# Sensor_Sheet.net
KiCad netlist of a schematic drawn in Altium Designer
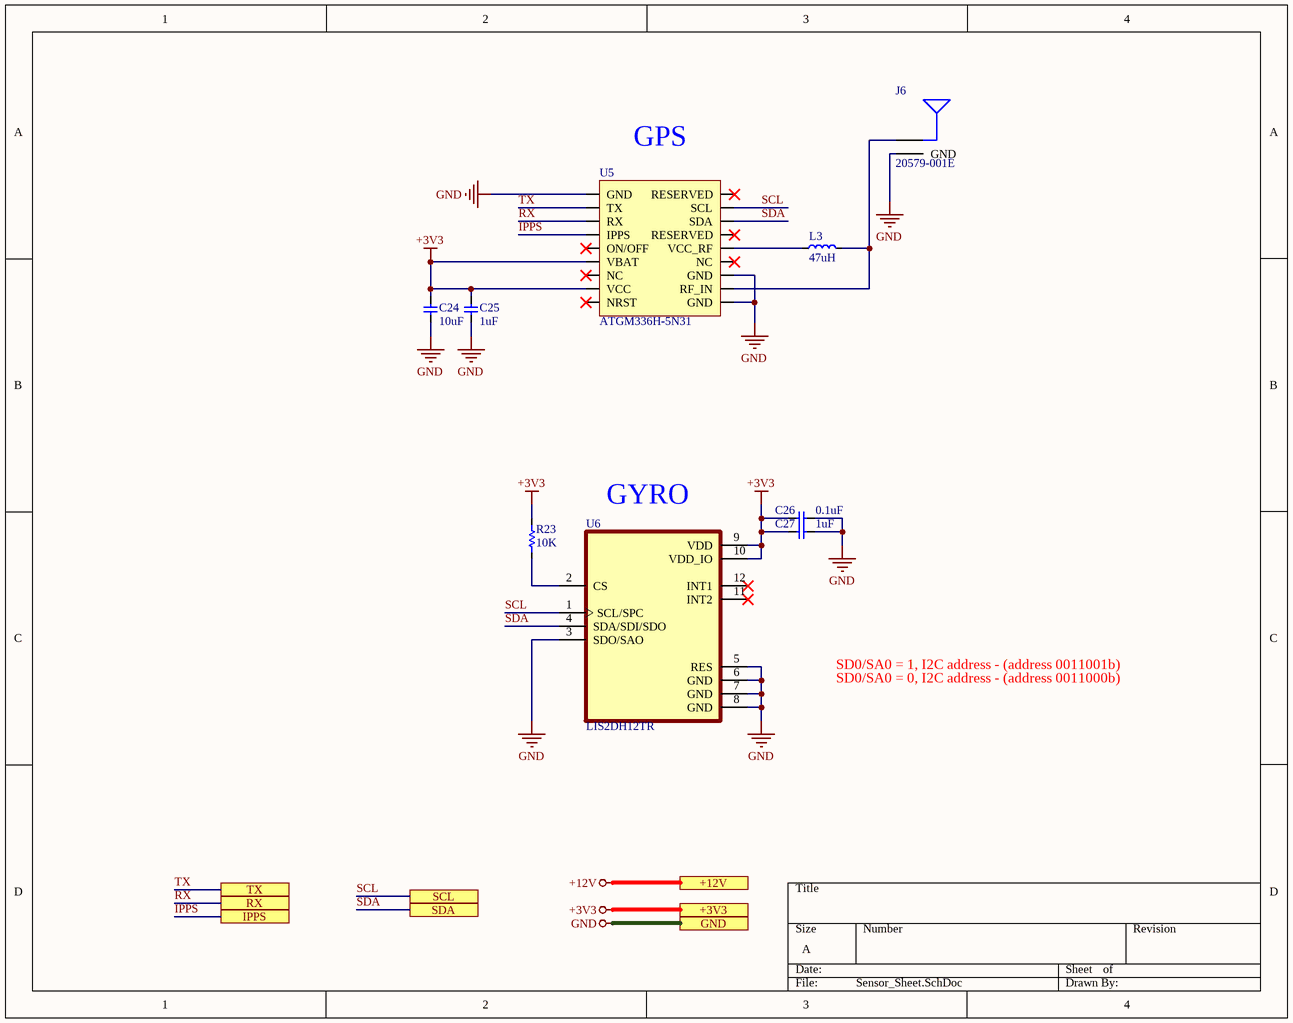
[diagram p0: Sensor_Sheet.SchDoc]

(export (version "E")
  (design (tool "Eeschema 10.0.6"))
  (components
    (comp (ref "C24")
      (value "10uF")
      (footprint "Cap-0603")
      (description "10uF 35V X5R 20% Pad SMD 0603")
      (fields
        (field (name "MANUFACTURER") "Murata")
        (field (name "MANUFACTURER PART NUMBER") "GRM188R6YA106MA73D")
      )
      (libsource (lib "DigitalAzanClock") (part "GRM188R6YA106MA73D"))
    )
    (comp (ref "C25")
      (value "1uF")
      (footprint "Cap-0603")
      (description "CAP CER 1UF 25V X5R 0603")
      (fields
        (field (name "MANUFACTURER") "Yageo")
        (field (name "MANUFACTURER PART NUMBER") "CC0603KRX5R8BB105")
      )
      (libsource (lib "DigitalAzanClock") (part "CC0603KRX5R8BB105"))
    )
    (comp (ref "C26")
      (value "0.1uF")
      (footprint "Cap-0603")
      (description "CAP CER 0.1UF 100V X7R 0603")
      (fields
        (field (name "MANUFACTURER") "Yageo")
        (field (name "MANUFACTURER PART NUMBER") "CC0603KRX7R0BB104")
      )
      (libsource (lib "DigitalAzanClock") (part "CC0603KRX7R0BB104"))
    )
    (comp (ref "C27")
      (value "1uF")
      (footprint "Cap-0603")
      (description "CAP CER 1UF 25V X5R 0603")
      (fields
        (field (name "MANUFACTURER") "Yageo")
        (field (name "MANUFACTURER PART NUMBER") "CC0603KRX5R8BB105")
      )
      (libsource (lib "DigitalAzanClock") (part "CC0603KRX5R8BB105"))
    )
    (comp (ref "J6")
      (value "20579-001E")
      (footprint "IPEX-1")
      (description "The M.2 industry standard,support up to 12 GHz")
      (fields (field (name "MANUFACTURER") "I-PEX") (field (name "LCSC PART NUMBER") "C2987682"))
      (libsource (lib "DigitalAzanClock") (part "IPEX-0001"))
    )
    (comp (ref "L3")
      (value "47uH")
      (footprint "CYA0650-47UH")
      (description "2A 47uH ±20% 250mΩ SMD,6.6x7.2mm Inductors (SMD) ROHS")
      (fields
        (field (name "MANUFACTURER") "SHOU HAN")
        (field (name "MANUFACTURER PART NUMBER") "CYA0650-47UH")
      )
      (libsource (lib "DigitalAzanClock") (part "CYA0650-47UH"))
    )
    (comp (ref "R23")
      (value "10K")
      (footprint "Res-0603")
      (description "RES SMD 10K OHM 0.1% 1/10W 0603")
      (fields
        (field (name "MANUFACTURER") "Yageo")
        (field (name "MANUFACTURER PART NUMBER") "RT0603BRD0710KL")
      )
      (libsource (lib "DigitalAzanClock") (part "RT0603BRD0710KL"))
    )
    (comp (ref "U5")
      (value "ATGM336H-5N31")
      (footprint "ATGM336H")
      (description "SMD,9.7x10.1mm Satellite Positioning Modules ROHS")
      (fields (field (name "MANUFACTURER") "ZHONGKEWEI") (field (name "LCSC PART NUMBER") "C90770"))
      (libsource (lib "DigitalAzanClock") (part "ATGM336H-5N31"))
    )
    (comp (ref "U6")
      (value "LIS2DH12TR")
      (footprint "PQFN50P200X200100-12N")
      (description "Accelerometer X, Y, Z Axis Â±2g, 4g, 8g, 16g 0.5Hz ~ 672Hz 12-LGA (2x2)")
      (fields (field (name "MANUFACTURER") "STMicroelectronics") (field (name "LCSC PART NUMBER") "C110926"))
      (libsource (lib "DigitalAzanClock") (part "LIS2DH12TR"))
    )
  )
  (nets
    (net (code "1") (name "+3V3") (class "Default")
      (node (ref "C24") (pin "2") (pinfunction "2_2") (pintype "passive"))
      (node (ref "C25") (pin "2") (pinfunction "2_2") (pintype "passive"))
      (node (ref "C26") (pin "1") (pinfunction "1_1") (pintype "passive"))
      (node (ref "C27") (pin "1") (pinfunction "1_1") (pintype "passive"))
      (node (ref "R23") (pin "2") (pinfunction "2_2") (pintype "passive"))
      (node (ref "U5") (pin "6") (pinfunction "VBAT_6") (pintype "passive"))
      (node (ref "U5") (pin "8") (pinfunction "VCC_8") (pintype "passive"))
      (node (ref "U6") (pin "10") (pinfunction "VDD_IO_10") (pintype "power_in"))
      (node (ref "U6") (pin "9") (pinfunction "VDD_9") (pintype "power_in"))
    )
    (net (code "3") (name "/IPPS") (class "Default")
      (node (ref "U5") (pin "4") (pinfunction "IPPS_4") (pintype "passive"))
    )
    (net (code "4") (name "/RX") (class "Default")
      (node (ref "U5") (pin "3") (pinfunction "RX_3") (pintype "passive"))
    )
    (net (code "5") (name "/SCL") (class "Default")
      (node (ref "U5") (pin "17") (pinfunction "SCL_17") (pintype "passive"))
      (node (ref "U6") (pin "1") (pinfunction "SCL/SPC_1") (pintype "passive"))
    )
    (net (code "6") (name "/SDA") (class "Default")
      (node (ref "U5") (pin "16") (pinfunction "SDA_16") (pintype "passive"))
      (node (ref "U6") (pin "4") (pinfunction "SDA/SDI/SDO_4") (pintype "passive"))
    )
    (net (code "7") (name "/TX") (class "Default")
      (node (ref "U5") (pin "2") (pinfunction "TX_2") (pintype "passive"))
    )
    (net (code "8") (name "GND") (class "Default")
      (node (ref "C24") (pin "1") (pinfunction "1_1") (pintype "passive"))
      (node (ref "C25") (pin "1") (pinfunction "1_1") (pintype "passive"))
      (node (ref "C26") (pin "2") (pinfunction "2_2") (pintype "passive"))
      (node (ref "C27") (pin "2") (pinfunction "2_2") (pintype "passive"))
      (node (ref "J6") (pin "2") (pinfunction "GND_2") (pintype "passive"))
      (node (ref "U5") (pin "1") (pinfunction "GND_1") (pintype "passive"))
      (node (ref "U5") (pin "10") (pinfunction "GND_10") (pintype "passive"))
      (node (ref "U5") (pin "12") (pinfunction "GND_12") (pintype "passive"))
      (node (ref "U6") (pin "3") (pinfunction "SDO/SAO_3") (pintype "passive"))
      (node (ref "U6") (pin "5") (pinfunction "RES_5") (pintype "power_in"))
      (node (ref "U6") (pin "6") (pinfunction "GND_6") (pintype "power_in"))
      (node (ref "U6") (pin "7") (pinfunction "GND_7") (pintype "power_in"))
      (node (ref "U6") (pin "8") (pinfunction "GND_8") (pintype "power_in"))
    )
    (net (code "9") (name "Net-(J6-SIGNAL)") (class "Default")
      (node (ref "J6") (pin "1") (pinfunction "SIGNAL_1") (pintype "passive"))
      (node (ref "L3") (pin "2") (pinfunction "2_2") (pintype "passive"))
      (node (ref "U5") (pin "11") (pinfunction "RF_IN_11") (pintype "passive"))
    )
    (net (code "10") (name "Net-(U5-VCC_RF)") (class "Default")
      (node (ref "L3") (pin "1") (pinfunction "1_1") (pintype "passive"))
      (node (ref "U5") (pin "14") (pinfunction "VCC_RF_14") (pintype "passive"))
    )
    (net (code "11") (name "Net-(U6-CS)") (class "Default")
      (node (ref "R23") (pin "1") (pinfunction "1_1") (pintype "passive"))
      (node (ref "U6") (pin "2") (pinfunction "CS_2") (pintype "passive"))
    )
    (net (code "12") (name "unconnected-(U5-NC-Pad7)") (class "Default")
      (node (ref "U5") (pin "7") (pinfunction "NC_7") (pintype "passive+no_connect"))
    )
    (net (code "13") (name "unconnected-(U5-NC-Pad13)") (class "Default")
      (node (ref "U5") (pin "13") (pinfunction "NC_13") (pintype "passive+no_connect"))
    )
    (net (code "14") (name "unconnected-(U5-NRST-Pad9)") (class "Default")
      (node (ref "U5") (pin "9") (pinfunction "NRST_9") (pintype "passive+no_connect"))
    )
    (net (code "15") (name "unconnected-(U5-ON{slash}OFF-Pad5)") (class "Default")
      (node (ref "U5") (pin "5") (pinfunction "ON/OFF_5") (pintype "passive+no_connect"))
    )
    (net (code "16") (name "unconnected-(U5-RESERVED-Pad15)") (class "Default")
      (node (ref "U5") (pin "15") (pinfunction "RESERVED_15") (pintype "passive+no_connect"))
    )
    (net (code "17") (name "unconnected-(U5-RESERVED-Pad18)") (class "Default")
      (node (ref "U5") (pin "18") (pinfunction "RESERVED_18") (pintype "passive+no_connect"))
    )
    (net (code "18") (name "unconnected-(U6-INT1-Pad12)") (class "Default")
      (node (ref "U6") (pin "12") (pinfunction "INT1_12") (pintype "passive+no_connect"))
    )
    (net (code "19") (name "unconnected-(U6-INT2-Pad11)") (class "Default")
      (node (ref "U6") (pin "11") (pinfunction "INT2_11") (pintype "passive+no_connect"))
    )
  )
)
